# DriveConnector.net
KiCad netlist of a schematic drawn in Altium Designer
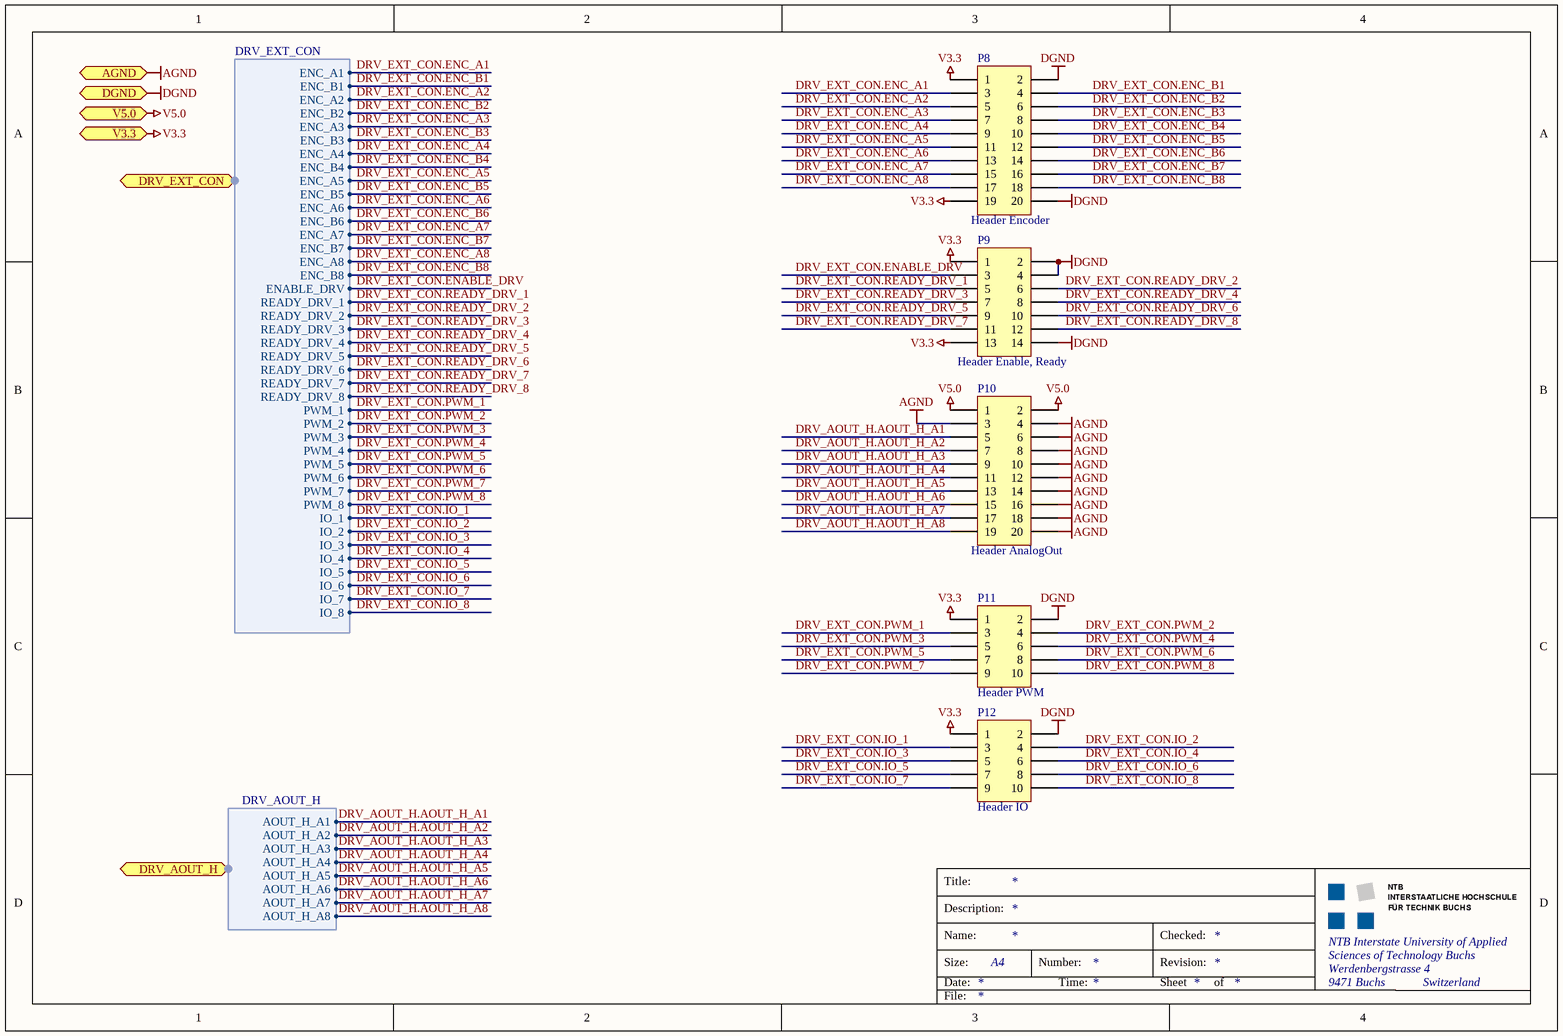
[diagram p0: DriveConnector.SchDoc]

(export (version "E")
  (design (tool "Eeschema 10.0.6"))
  (components
    (comp (ref "P8")
      (value "Header Encoder")
      (footprint "Wannenstecker 2x10 - H")
      (description "Header, 10-Pin, Dual row")
      (fields (field (name "PUBLISHER") "Altium Limited"))
      (libsource (lib "Miscellaneous Connectors") (part "Header 10X2"))
    )
    (comp (ref "P9")
      (value "Header Enable, Ready")
      (footprint "Wannenstecker 2x7 - H")
      (description "Header, 7-Pin, Dual row")
      (fields (field (name "PUBLISHER") "Altium Limited"))
      (libsource (lib "inf") (part "Header 2x7"))
    )
    (comp (ref "P10")
      (value "Header AnalogOut")
      (footprint "Wannenstecker 2x10 - H")
      (description "Header, 10-Pin, Dual row")
      (fields (field (name "PUBLISHER") "Altium Limited"))
      (libsource (lib "Miscellaneous Connectors") (part "Header 10X2"))
    )
    (comp (ref "P11")
      (value "Header PWM")
      (footprint "Wannenstecker 2x5 - H")
      (description "Header, 5-Pin, Dual row")
      (fields (field (name "PUBLISHER") "Altium Limited"))
      (libsource (lib "Miscellaneous Connectors") (part "Header 5X2"))
    )
    (comp (ref "P12")
      (value "Header IO")
      (footprint "Wannenstecker 2x5 - H")
      (description "Header, 5-Pin, Dual row")
      (fields (field (name "PUBLISHER") "Altium Limited"))
      (libsource (lib "Miscellaneous Connectors") (part "Header 5X2"))
    )
  )
  (nets
    (net (code "3") (name "/DRV_AOUT_H.AOUT_H_A1") (class "Default")
      (node (ref "P10") (pin "5") (pinfunction "5_5") (pintype "passive"))
    )
    (net (code "4") (name "/DRV_AOUT_H.AOUT_H_A2") (class "Default")
      (node (ref "P10") (pin "7") (pinfunction "7_7") (pintype "passive"))
    )
    (net (code "5") (name "/DRV_AOUT_H.AOUT_H_A3") (class "Default")
      (node (ref "P10") (pin "9") (pinfunction "9_9") (pintype "passive"))
    )
    (net (code "6") (name "/DRV_AOUT_H.AOUT_H_A4") (class "Default")
      (node (ref "P10") (pin "11") (pinfunction "11_11") (pintype "passive"))
    )
    (net (code "7") (name "/DRV_AOUT_H.AOUT_H_A5") (class "Default")
      (node (ref "P10") (pin "13") (pinfunction "13_13") (pintype "passive"))
    )
    (net (code "8") (name "/DRV_AOUT_H.AOUT_H_A6") (class "Default")
      (node (ref "P10") (pin "15") (pinfunction "15_15") (pintype "passive"))
    )
    (net (code "9") (name "/DRV_AOUT_H.AOUT_H_A7") (class "Default")
      (node (ref "P10") (pin "17") (pinfunction "17_17") (pintype "passive"))
    )
    (net (code "10") (name "/DRV_AOUT_H.AOUT_H_A8") (class "Default")
      (node (ref "P10") (pin "19") (pinfunction "19_19") (pintype "passive"))
    )
    (net (code "11") (name "/DRV_EXT_CON.ENABLE_DRV") (class "Default")
      (node (ref "P9") (pin "3") (pinfunction "3_3") (pintype "passive"))
    )
    (net (code "12") (name "/DRV_EXT_CON.ENC_A1") (class "Default")
      (node (ref "P8") (pin "3") (pinfunction "3_3") (pintype "passive"))
    )
    (net (code "13") (name "/DRV_EXT_CON.ENC_A2") (class "Default")
      (node (ref "P8") (pin "5") (pinfunction "5_5") (pintype "passive"))
    )
    (net (code "14") (name "/DRV_EXT_CON.ENC_A3") (class "Default")
      (node (ref "P8") (pin "7") (pinfunction "7_7") (pintype "passive"))
    )
    (net (code "15") (name "/DRV_EXT_CON.ENC_A4") (class "Default")
      (node (ref "P8") (pin "9") (pinfunction "9_9") (pintype "passive"))
    )
    (net (code "16") (name "/DRV_EXT_CON.ENC_A5") (class "Default")
      (node (ref "P8") (pin "11") (pinfunction "11_11") (pintype "passive"))
    )
    (net (code "17") (name "/DRV_EXT_CON.ENC_A6") (class "Default")
      (node (ref "P8") (pin "13") (pinfunction "13_13") (pintype "passive"))
    )
    (net (code "18") (name "/DRV_EXT_CON.ENC_A7") (class "Default")
      (node (ref "P8") (pin "15") (pinfunction "15_15") (pintype "passive"))
    )
    (net (code "19") (name "/DRV_EXT_CON.ENC_A8") (class "Default")
      (node (ref "P8") (pin "17") (pinfunction "17_17") (pintype "passive"))
    )
    (net (code "20") (name "/DRV_EXT_CON.ENC_B1") (class "Default")
      (node (ref "P8") (pin "4") (pinfunction "4_4") (pintype "passive"))
    )
    (net (code "21") (name "/DRV_EXT_CON.ENC_B2") (class "Default")
      (node (ref "P8") (pin "6") (pinfunction "6_6") (pintype "passive"))
    )
    (net (code "22") (name "/DRV_EXT_CON.ENC_B3") (class "Default")
      (node (ref "P8") (pin "8") (pinfunction "8_8") (pintype "passive"))
    )
    (net (code "23") (name "/DRV_EXT_CON.ENC_B4") (class "Default")
      (node (ref "P8") (pin "10") (pinfunction "10_10") (pintype "passive"))
    )
    (net (code "24") (name "/DRV_EXT_CON.ENC_B5") (class "Default")
      (node (ref "P8") (pin "12") (pinfunction "12_12") (pintype "passive"))
    )
    (net (code "25") (name "/DRV_EXT_CON.ENC_B6") (class "Default")
      (node (ref "P8") (pin "14") (pinfunction "14_14") (pintype "passive"))
    )
    (net (code "26") (name "/DRV_EXT_CON.ENC_B7") (class "Default")
      (node (ref "P8") (pin "16") (pinfunction "16_16") (pintype "passive"))
    )
    (net (code "27") (name "/DRV_EXT_CON.ENC_B8") (class "Default")
      (node (ref "P8") (pin "18") (pinfunction "18_18") (pintype "passive"))
    )
    (net (code "28") (name "/DRV_EXT_CON.IO_1") (class "Default")
      (node (ref "P12") (pin "3") (pinfunction "3_3") (pintype "passive"))
    )
    (net (code "29") (name "/DRV_EXT_CON.IO_2") (class "Default")
      (node (ref "P12") (pin "4") (pinfunction "4_4") (pintype "passive"))
    )
    (net (code "30") (name "/DRV_EXT_CON.IO_3") (class "Default")
      (node (ref "P12") (pin "5") (pinfunction "5_5") (pintype "passive"))
    )
    (net (code "31") (name "/DRV_EXT_CON.IO_4") (class "Default")
      (node (ref "P12") (pin "6") (pinfunction "6_6") (pintype "passive"))
    )
    (net (code "32") (name "/DRV_EXT_CON.IO_5") (class "Default")
      (node (ref "P12") (pin "7") (pinfunction "7_7") (pintype "passive"))
    )
    (net (code "33") (name "/DRV_EXT_CON.IO_6") (class "Default")
      (node (ref "P12") (pin "8") (pinfunction "8_8") (pintype "passive"))
    )
    (net (code "34") (name "/DRV_EXT_CON.IO_7") (class "Default")
      (node (ref "P12") (pin "9") (pinfunction "9_9") (pintype "passive"))
    )
    (net (code "35") (name "/DRV_EXT_CON.IO_8") (class "Default")
      (node (ref "P12") (pin "10") (pinfunction "10_10") (pintype "passive"))
    )
    (net (code "36") (name "/DRV_EXT_CON.PWM_1") (class "Default")
      (node (ref "P11") (pin "3") (pinfunction "3_3") (pintype "passive"))
    )
    (net (code "37") (name "/DRV_EXT_CON.PWM_2") (class "Default")
      (node (ref "P11") (pin "4") (pinfunction "4_4") (pintype "passive"))
    )
    (net (code "38") (name "/DRV_EXT_CON.PWM_3") (class "Default")
      (node (ref "P11") (pin "5") (pinfunction "5_5") (pintype "passive"))
    )
    (net (code "39") (name "/DRV_EXT_CON.PWM_4") (class "Default")
      (node (ref "P11") (pin "6") (pinfunction "6_6") (pintype "passive"))
    )
    (net (code "40") (name "/DRV_EXT_CON.PWM_5") (class "Default")
      (node (ref "P11") (pin "7") (pinfunction "7_7") (pintype "passive"))
    )
    (net (code "41") (name "/DRV_EXT_CON.PWM_6") (class "Default")
      (node (ref "P11") (pin "8") (pinfunction "8_8") (pintype "passive"))
    )
    (net (code "42") (name "/DRV_EXT_CON.PWM_7") (class "Default")
      (node (ref "P11") (pin "9") (pinfunction "9_9") (pintype "passive"))
    )
    (net (code "43") (name "/DRV_EXT_CON.PWM_8") (class "Default")
      (node (ref "P11") (pin "10") (pinfunction "10_10") (pintype "passive"))
    )
    (net (code "44") (name "/DRV_EXT_CON.READY_DRV_1") (class "Default")
      (node (ref "P9") (pin "5") (pinfunction "5_5") (pintype "passive"))
    )
    (net (code "45") (name "/DRV_EXT_CON.READY_DRV_2") (class "Default")
      (node (ref "P9") (pin "6") (pinfunction "6_6") (pintype "passive"))
    )
    (net (code "46") (name "/DRV_EXT_CON.READY_DRV_3") (class "Default")
      (node (ref "P9") (pin "7") (pinfunction "7_7") (pintype "passive"))
    )
    (net (code "47") (name "/DRV_EXT_CON.READY_DRV_4") (class "Default")
      (node (ref "P9") (pin "8") (pinfunction "8_8") (pintype "passive"))
    )
    (net (code "48") (name "/DRV_EXT_CON.READY_DRV_5") (class "Default")
      (node (ref "P9") (pin "9") (pinfunction "9_9") (pintype "passive"))
    )
    (net (code "49") (name "/DRV_EXT_CON.READY_DRV_6") (class "Default")
      (node (ref "P9") (pin "10") (pinfunction "10_10") (pintype "passive"))
    )
    (net (code "50") (name "/DRV_EXT_CON.READY_DRV_7") (class "Default")
      (node (ref "P9") (pin "11") (pinfunction "11_11") (pintype "passive"))
    )
    (net (code "51") (name "/DRV_EXT_CON.READY_DRV_8") (class "Default")
      (node (ref "P9") (pin "12") (pinfunction "12_12") (pintype "passive"))
    )
    (net (code "54") (name "AGND") (class "Default")
      (node (ref "P10") (pin "10") (pinfunction "10_10") (pintype "passive"))
      (node (ref "P10") (pin "12") (pinfunction "12_12") (pintype "passive"))
      (node (ref "P10") (pin "14") (pinfunction "14_14") (pintype "passive"))
      (node (ref "P10") (pin "16") (pinfunction "16_16") (pintype "passive"))
      (node (ref "P10") (pin "18") (pinfunction "18_18") (pintype "passive"))
      (node (ref "P10") (pin "20") (pinfunction "20_20") (pintype "passive"))
      (node (ref "P10") (pin "3") (pinfunction "3_3") (pintype "passive"))
      (node (ref "P10") (pin "4") (pinfunction "4_4") (pintype "passive"))
      (node (ref "P10") (pin "6") (pinfunction "6_6") (pintype "passive"))
      (node (ref "P10") (pin "8") (pinfunction "8_8") (pintype "passive"))
    )
    (net (code "55") (name "DGND") (class "Default")
      (node (ref "P11") (pin "2") (pinfunction "2_2") (pintype "passive"))
      (node (ref "P12") (pin "2") (pinfunction "2_2") (pintype "passive"))
      (node (ref "P8") (pin "2") (pinfunction "2_2") (pintype "passive"))
      (node (ref "P8") (pin "20") (pinfunction "20_20") (pintype "passive"))
      (node (ref "P9") (pin "14") (pinfunction "14_14") (pintype "passive"))
      (node (ref "P9") (pin "2") (pinfunction "2_2") (pintype "passive"))
      (node (ref "P9") (pin "4") (pinfunction "4_4") (pintype "passive"))
    )
    (net (code "56") (name "V3.3") (class "Default")
      (node (ref "P11") (pin "1") (pinfunction "1_1") (pintype "passive"))
      (node (ref "P12") (pin "1") (pinfunction "1_1") (pintype "passive"))
      (node (ref "P8") (pin "1") (pinfunction "1_1") (pintype "passive"))
      (node (ref "P8") (pin "19") (pinfunction "19_19") (pintype "passive"))
      (node (ref "P9") (pin "1") (pinfunction "1_1") (pintype "passive"))
      (node (ref "P9") (pin "13") (pinfunction "13_13") (pintype "passive"))
    )
    (net (code "57") (name "V5.0") (class "Default")
      (node (ref "P10") (pin "1") (pinfunction "1_1") (pintype "passive"))
      (node (ref "P10") (pin "2") (pinfunction "2_2") (pintype "passive"))
    )
  )
)
